# Quadrature_Mixers_FIXED.net
KiCad netlist of a schematic drawn in Altium Designer
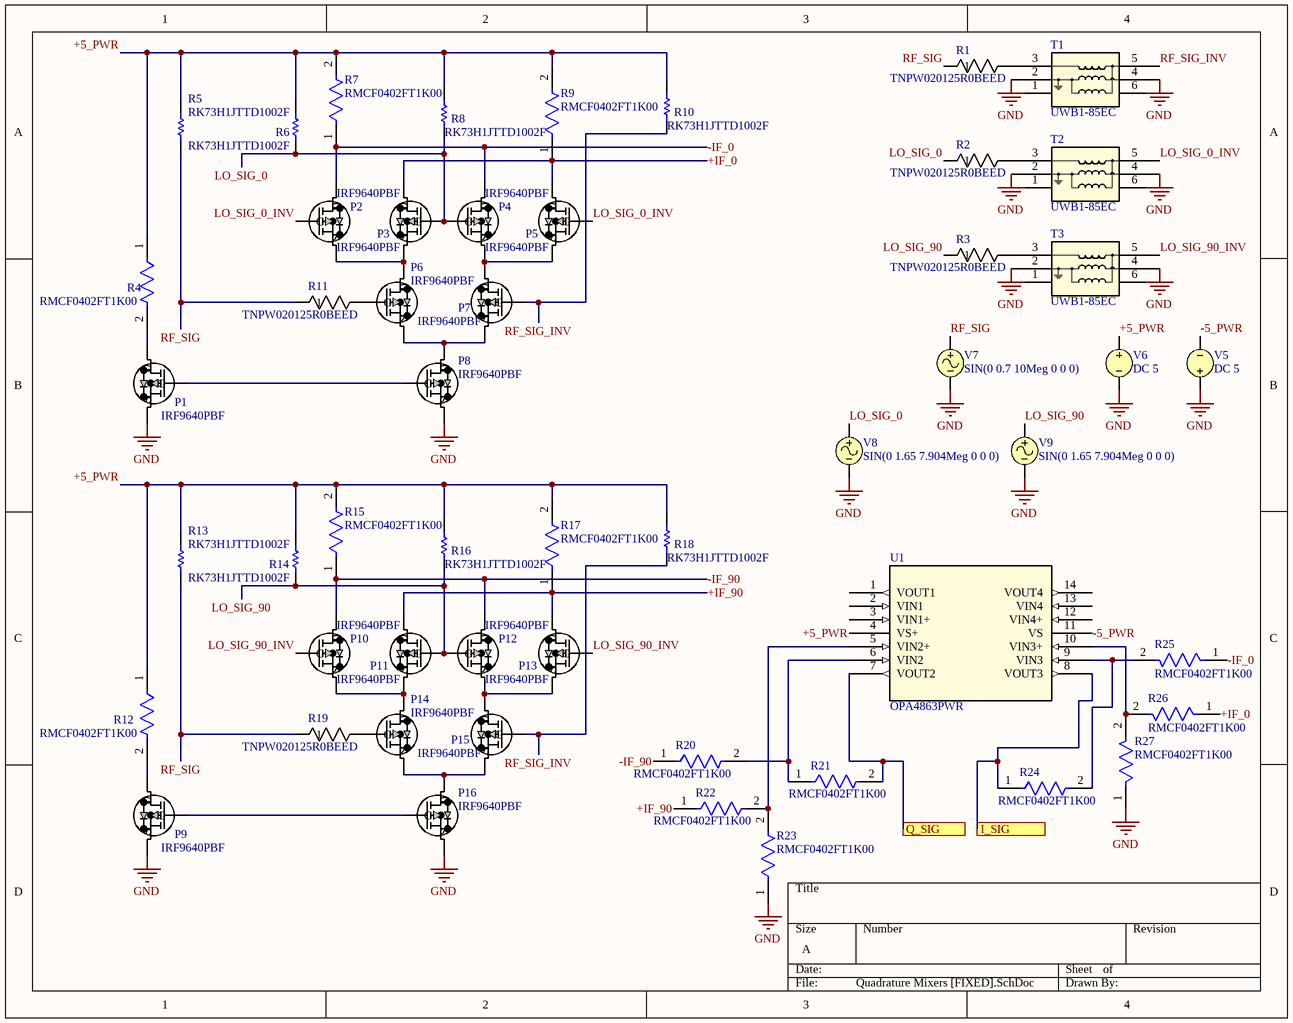
[diagram p0: Quadrature Mixers [FIXED].SchDoc]

(export (version "E")
  (design (tool "Eeschema 10.0.6"))
  (components
    (comp (ref "P1")
      (value "IRF9640PBF")
      (footprint "TO220AB_VIS")
      (description "No Description Available")
      (libsource (lib "IRF9640PBF") (part "IRF9640PBF"))
    )
    (comp (ref "P2")
      (value "IRF9640PBF")
      (footprint "TO220AB_VIS")
      (description "No Description Available")
      (libsource (lib "IRF9640PBF") (part "IRF9640PBF"))
    )
    (comp (ref "P3")
      (value "IRF9640PBF")
      (footprint "TO220AB_VIS")
      (description "No Description Available")
      (libsource (lib "IRF9640PBF") (part "IRF9640PBF"))
    )
    (comp (ref "P4")
      (value "IRF9640PBF")
      (footprint "TO220AB_VIS")
      (description "No Description Available")
      (libsource (lib "IRF9640PBF") (part "IRF9640PBF"))
    )
    (comp (ref "P5")
      (value "IRF9640PBF")
      (footprint "TO220AB_VIS")
      (description "No Description Available")
      (libsource (lib "IRF9640PBF") (part "IRF9640PBF"))
    )
    (comp (ref "P6")
      (value "IRF9640PBF")
      (footprint "TO220AB_VIS")
      (description "No Description Available")
      (libsource (lib "IRF9640PBF") (part "IRF9640PBF"))
    )
    (comp (ref "P7")
      (value "IRF9640PBF")
      (footprint "TO220AB_VIS")
      (description "No Description Available")
      (libsource (lib "IRF9640PBF") (part "IRF9640PBF"))
    )
    (comp (ref "P8")
      (value "IRF9640PBF")
      (footprint "TO220AB_VIS")
      (description "No Description Available")
      (libsource (lib "IRF9640PBF") (part "IRF9640PBF"))
    )
    (comp (ref "P9")
      (value "IRF9640PBF")
      (footprint "TO220AB_VIS")
      (description "No Description Available")
      (libsource (lib "IRF9640PBF") (part "IRF9640PBF"))
    )
    (comp (ref "P10")
      (value "IRF9640PBF")
      (footprint "TO220AB_VIS")
      (description "No Description Available")
      (libsource (lib "IRF9640PBF") (part "IRF9640PBF"))
    )
    (comp (ref "P11")
      (value "IRF9640PBF")
      (footprint "TO220AB_VIS")
      (description "No Description Available")
      (libsource (lib "IRF9640PBF") (part "IRF9640PBF"))
    )
    (comp (ref "P12")
      (value "IRF9640PBF")
      (footprint "TO220AB_VIS")
      (description "No Description Available")
      (libsource (lib "IRF9640PBF") (part "IRF9640PBF"))
    )
    (comp (ref "P13")
      (value "IRF9640PBF")
      (footprint "TO220AB_VIS")
      (description "No Description Available")
      (libsource (lib "IRF9640PBF") (part "IRF9640PBF"))
    )
    (comp (ref "P14")
      (value "IRF9640PBF")
      (footprint "TO220AB_VIS")
      (description "No Description Available")
      (libsource (lib "IRF9640PBF") (part "IRF9640PBF"))
    )
    (comp (ref "P15")
      (value "IRF9640PBF")
      (footprint "TO220AB_VIS")
      (description "No Description Available")
      (libsource (lib "IRF9640PBF") (part "IRF9640PBF"))
    )
    (comp (ref "P16")
      (value "IRF9640PBF")
      (footprint "TO220AB_VIS")
      (description "No Description Available")
      (libsource (lib "IRF9640PBF") (part "IRF9640PBF"))
    )
    (comp (ref "R1")
      (value "TNPW020125R0BEED")
      (footprint "RES_TNPW0201_VIS")
      (description "RES 25 OHM 0.1% 0.075W 0201")
      (libsource (lib "TNPW020125R0BEED") (part "TNPW020125R0BEED"))
    )
    (comp (ref "R2")
      (value "TNPW020125R0BEED")
      (footprint "RES_TNPW0201_VIS")
      (description "RES 25 OHM 0.1% 0.075W 0201")
      (libsource (lib "TNPW020125R0BEED") (part "TNPW020125R0BEED"))
    )
    (comp (ref "R3")
      (value "TNPW020125R0BEED")
      (footprint "RES_TNPW0201_VIS")
      (description "RES 25 OHM 0.1% 0.075W 0201")
      (libsource (lib "TNPW020125R0BEED") (part "TNPW020125R0BEED"))
    )
    (comp (ref "R4")
      (value "RMCF0402FT1K00")
      (footprint "FP-RMCF0402-MFG")
      (description "1kΩ ±1% 0.063W 0402 Thick Film Chip Resistor AEC-Q200 compliant")
      (fields (field (name "TOLERANCE") "1%"))
      (libsource (lib "Altium Content Vault") (part "1029c3af85768c4190bb7ad29bc67b5"))
    )
    (comp (ref "R5")
      (value "RK73H1JTTD1002F")
      (footprint "RESC1608X55X30ML20T10")
      (fields (field (name "MANUFACTURER") "KOA Speer"))
      (libsource (lib "Altium Content Vault") (part "RES"))
    )
    (comp (ref "R6")
      (value "RK73H1JTTD1002F")
      (footprint "RESC1608X55X30ML20T10")
      (fields (field (name "MANUFACTURER") "KOA Speer"))
      (libsource (lib "Altium Content Vault") (part "RES"))
    )
    (comp (ref "R7")
      (value "RMCF0402FT1K00")
      (footprint "FP-RMCF0402-MFG")
      (description "1kΩ ±1% 0.063W 0402 Thick Film Chip Resistor AEC-Q200 compliant")
      (fields (field (name "TOLERANCE") "1%"))
      (libsource (lib "Altium Content Vault") (part "1029c3af85768c4190bb7ad29bc67b5"))
    )
    (comp (ref "R8")
      (value "RK73H1JTTD1002F")
      (footprint "RESC1608X55X30ML20T10")
      (fields (field (name "MANUFACTURER") "KOA Speer"))
      (libsource (lib "Altium Content Vault") (part "RES"))
    )
    (comp (ref "R9")
      (value "RMCF0402FT1K00")
      (footprint "FP-RMCF0402-MFG")
      (description "1kΩ ±1% 0.063W 0402 Thick Film Chip Resistor AEC-Q200 compliant")
      (fields (field (name "TOLERANCE") "1%"))
      (libsource (lib "Altium Content Vault") (part "1029c3af85768c4190bb7ad29bc67b5"))
    )
    (comp (ref "R10")
      (value "RK73H1JTTD1002F")
      (footprint "RESC1608X55X30ML20T10")
      (fields (field (name "MANUFACTURER") "KOA Speer"))
      (libsource (lib "Altium Content Vault") (part "RES"))
    )
    (comp (ref "R11")
      (value "TNPW020125R0BEED")
      (footprint "RES_TNPW0201_VIS")
      (description "RES 25 OHM 0.1% 0.075W 0201")
      (libsource (lib "TNPW020125R0BEED") (part "TNPW020125R0BEED"))
    )
    (comp (ref "R12")
      (value "RMCF0402FT1K00")
      (footprint "FP-RMCF0402-MFG")
      (description "1kΩ ±1% 0.063W 0402 Thick Film Chip Resistor AEC-Q200 compliant")
      (fields (field (name "TOLERANCE") "1%"))
      (libsource (lib "Altium Content Vault") (part "1029c3af85768c4190bb7ad29bc67b5"))
    )
    (comp (ref "R13")
      (value "RK73H1JTTD1002F")
      (footprint "RESC1608X55X30ML20T10")
      (fields (field (name "MANUFACTURER") "KOA Speer"))
      (libsource (lib "Altium Content Vault") (part "RES"))
    )
    (comp (ref "R14")
      (value "RK73H1JTTD1002F")
      (footprint "RESC1608X55X30ML20T10")
      (fields (field (name "MANUFACTURER") "KOA Speer"))
      (libsource (lib "Altium Content Vault") (part "RES"))
    )
    (comp (ref "R15")
      (value "RMCF0402FT1K00")
      (footprint "FP-RMCF0402-MFG")
      (description "1kΩ ±1% 0.063W 0402 Thick Film Chip Resistor AEC-Q200 compliant")
      (fields (field (name "TOLERANCE") "1%"))
      (libsource (lib "Altium Content Vault") (part "1029c3af85768c4190bb7ad29bc67b5"))
    )
    (comp (ref "R16")
      (value "RK73H1JTTD1002F")
      (footprint "RESC1608X55X30ML20T10")
      (fields (field (name "MANUFACTURER") "KOA Speer"))
      (libsource (lib "Altium Content Vault") (part "RES"))
    )
    (comp (ref "R17")
      (value "RMCF0402FT1K00")
      (footprint "FP-RMCF0402-MFG")
      (description "1kΩ ±1% 0.063W 0402 Thick Film Chip Resistor AEC-Q200 compliant")
      (fields (field (name "TOLERANCE") "1%"))
      (libsource (lib "Altium Content Vault") (part "1029c3af85768c4190bb7ad29bc67b5"))
    )
    (comp (ref "R18")
      (value "RK73H1JTTD1002F")
      (footprint "RESC1608X55X30ML20T10")
      (fields (field (name "MANUFACTURER") "KOA Speer"))
      (libsource (lib "Altium Content Vault") (part "RES"))
    )
    (comp (ref "R19")
      (value "TNPW020125R0BEED")
      (footprint "RES_TNPW0201_VIS")
      (description "RES 25 OHM 0.1% 0.075W 0201")
      (libsource (lib "TNPW020125R0BEED") (part "TNPW020125R0BEED"))
    )
    (comp (ref "R20")
      (value "RMCF0402FT1K00")
      (footprint "FP-RMCF0402-MFG")
      (description "1kΩ ±1% 0.063W 0402 Thick Film Chip Resistor AEC-Q200 compliant")
      (fields (field (name "TOLERANCE") "1%"))
      (libsource (lib "Altium Content Vault") (part "1029c3af85768c4190bb7ad29bc67b5"))
    )
    (comp (ref "R21")
      (value "RMCF0402FT1K00")
      (footprint "FP-RMCF0402-MFG")
      (description "1kΩ ±1% 0.063W 0402 Thick Film Chip Resistor AEC-Q200 compliant")
      (fields (field (name "TOLERANCE") "1%"))
      (libsource (lib "Altium Content Vault") (part "1029c3af85768c4190bb7ad29bc67b5"))
    )
    (comp (ref "R22")
      (value "RMCF0402FT1K00")
      (footprint "FP-RMCF0402-MFG")
      (description "1kΩ ±1% 0.063W 0402 Thick Film Chip Resistor AEC-Q200 compliant")
      (fields (field (name "TOLERANCE") "1%"))
      (libsource (lib "Altium Content Vault") (part "1029c3af85768c4190bb7ad29bc67b5"))
    )
    (comp (ref "R23")
      (value "RMCF0402FT1K00")
      (footprint "FP-RMCF0402-MFG")
      (description "1kΩ ±1% 0.063W 0402 Thick Film Chip Resistor AEC-Q200 compliant")
      (fields (field (name "TOLERANCE") "1%"))
      (libsource (lib "Altium Content Vault") (part "1029c3af85768c4190bb7ad29bc67b5"))
    )
    (comp (ref "R24")
      (value "RMCF0402FT1K00")
      (footprint "FP-RMCF0402-MFG")
      (description "1kΩ ±1% 0.063W 0402 Thick Film Chip Resistor AEC-Q200 compliant")
      (fields (field (name "TOLERANCE") "1%"))
      (libsource (lib "Altium Content Vault") (part "1029c3af85768c4190bb7ad29bc67b5"))
    )
    (comp (ref "R25")
      (value "RMCF0402FT1K00")
      (footprint "FP-RMCF0402-MFG")
      (description "1kΩ ±1% 0.063W 0402 Thick Film Chip Resistor AEC-Q200 compliant")
      (fields (field (name "TOLERANCE") "1%"))
      (libsource (lib "Altium Content Vault") (part "1029c3af85768c4190bb7ad29bc67b5"))
    )
    (comp (ref "R26")
      (value "RMCF0402FT1K00")
      (footprint "FP-RMCF0402-MFG")
      (description "1kΩ ±1% 0.063W 0402 Thick Film Chip Resistor AEC-Q200 compliant")
      (fields (field (name "TOLERANCE") "1%"))
      (libsource (lib "Altium Content Vault") (part "1029c3af85768c4190bb7ad29bc67b5"))
    )
    (comp (ref "R27")
      (value "RMCF0402FT1K00")
      (footprint "FP-RMCF0402-MFG")
      (description "1kΩ ±1% 0.063W 0402 Thick Film Chip Resistor AEC-Q200 compliant")
      (fields (field (name "TOLERANCE") "1%"))
      (libsource (lib "Altium Content Vault") (part "1029c3af85768c4190bb7ad29bc67b5"))
    )
    (comp (ref "T1")
      (value "UWB1-85EC")
      (footprint "UWB1UWB2_COC")
      (libsource (lib "UWB1-85EC") (part "UWB1-85EC"))
    )
    (comp (ref "T2")
      (value "UWB1-85EC")
      (footprint "UWB1UWB2_COC")
      (libsource (lib "UWB1-85EC") (part "UWB1-85EC"))
    )
    (comp (ref "T3")
      (value "UWB1-85EC")
      (footprint "UWB1UWB2_COC")
      (libsource (lib "UWB1-85EC") (part "UWB1-85EC"))
    )
    (comp (ref "U1")
      (value "OPA4863PWR")
      (footprint "PW14_TEX")
      (description "No Description Available")
      (libsource (lib "OPA4863PWR") (part "OPA4863PWR"))
    )
    (comp (ref "V5")
      (value "DC 5")
      (description "Voltage Source")
      (fields (field (name "PUBLISHER") "Altium Limited"))
      (libsource (lib "Simulation Generic Components") (part "VSRC"))
    )
    (comp (ref "V6")
      (value "DC 5")
      (description "Voltage Source")
      (fields (field (name "PUBLISHER") "Altium Limited"))
      (libsource (lib "Simulation Generic Components") (part "VSRC"))
    )
    (comp (ref "V7")
      (value "SIN(0 0.7 10Meg 0 0 0)")
      (description "Sinusoidal Voltage Source")
      (fields (field (name "PUBLISHER") "Altium Limited"))
      (libsource (lib "Simulation Generic Components") (part "VSIN"))
    )
    (comp (ref "V8")
      (value "SIN(0 1.65 7.904Meg 0 0 0)")
      (description "Sinusoidal Voltage Source")
      (fields (field (name "PUBLISHER") "Altium Limited"))
      (libsource (lib "Simulation Generic Components") (part "VSIN"))
    )
    (comp (ref "V9")
      (value "SIN(0 1.65 7.904Meg 0 0 0)")
      (description "Sinusoidal Voltage Source")
      (fields (field (name "PUBLISHER") "Altium Limited"))
      (libsource (lib "Simulation Generic Components") (part "VSIN"))
    )
  )
  (nets
    (net (code "1") (name "/+5_PWR") (class "Default")
      (node (ref "R10") (pin "2") (pinfunction "2_2") (pintype "passive"))
      (node (ref "R12") (pin "1") (pinfunction "1_1") (pintype "passive"))
      (node (ref "R13") (pin "2") (pinfunction "2_2") (pintype "passive"))
      (node (ref "R14") (pin "2") (pinfunction "2_2") (pintype "passive"))
      (node (ref "R15") (pin "2") (pinfunction "2_2") (pintype "passive"))
      (node (ref "R16") (pin "2") (pinfunction "2_2") (pintype "passive"))
      (node (ref "R17") (pin "2") (pinfunction "2_2") (pintype "passive"))
      (node (ref "R18") (pin "2") (pinfunction "2_2") (pintype "passive"))
      (node (ref "R4") (pin "1") (pinfunction "1_1") (pintype "passive"))
      (node (ref "R5") (pin "2") (pinfunction "2_2") (pintype "passive"))
      (node (ref "R6") (pin "2") (pinfunction "2_2") (pintype "passive"))
      (node (ref "R7") (pin "2") (pinfunction "2_2") (pintype "passive"))
      (node (ref "R8") (pin "2") (pinfunction "2_2") (pintype "passive"))
      (node (ref "R9") (pin "2") (pinfunction "2_2") (pintype "passive"))
      (node (ref "U1") (pin "4") (pinfunction "VS+_4") (pintype "power_in"))
      (node (ref "V6") (pin "1") (pinfunction "1_1") (pintype "passive"))
    )
    (net (code "2") (name "/+IF_0") (class "Default")
      (node (ref "P3") (pin "2") (pinfunction "D_2") (pintype "passive"))
      (node (ref "P5") (pin "2") (pinfunction "D_2") (pintype "passive"))
      (node (ref "R26") (pin "1") (pinfunction "1_1") (pintype "passive"))
      (node (ref "R9") (pin "1") (pinfunction "1_1") (pintype "passive"))
    )
    (net (code "3") (name "/+IF_90") (class "Default")
      (node (ref "P11") (pin "2") (pinfunction "D_2") (pintype "passive"))
      (node (ref "P13") (pin "2") (pinfunction "D_2") (pintype "passive"))
      (node (ref "R17") (pin "1") (pinfunction "1_1") (pintype "passive"))
      (node (ref "R22") (pin "1") (pinfunction "1_1") (pintype "passive"))
    )
    (net (code "4") (name "/-5_PWR") (class "Default")
      (node (ref "U1") (pin "11") (pinfunction "VS_11") (pintype "power_in"))
      (node (ref "V5") (pin "2") (pinfunction "2_2") (pintype "passive"))
    )
    (net (code "5") (name "/-IF_0") (class "Default")
      (node (ref "P2") (pin "2") (pinfunction "D_2") (pintype "passive"))
      (node (ref "P4") (pin "2") (pinfunction "D_2") (pintype "passive"))
      (node (ref "R25") (pin "1") (pinfunction "1_1") (pintype "passive"))
      (node (ref "R7") (pin "1") (pinfunction "1_1") (pintype "passive"))
    )
    (net (code "6") (name "/-IF_90") (class "Default")
      (node (ref "P10") (pin "2") (pinfunction "D_2") (pintype "passive"))
      (node (ref "P12") (pin "2") (pinfunction "D_2") (pintype "passive"))
      (node (ref "R15") (pin "1") (pinfunction "1_1") (pintype "passive"))
      (node (ref "R20") (pin "1") (pinfunction "1_1") (pintype "passive"))
    )
    (net (code "7") (name "/I_SIG") (class "Default")
      (node (ref "R24") (pin "1") (pinfunction "1_1") (pintype "passive"))
      (node (ref "U1") (pin "8") (pinfunction "VOUT3_8") (pintype "output"))
    )
    (net (code "8") (name "/LO_SIG_0") (class "Default")
      (node (ref "P3") (pin "1") (pinfunction "G_1") (pintype "passive"))
      (node (ref "P4") (pin "1") (pinfunction "G_1") (pintype "passive"))
      (node (ref "R2") (pin "1") (pinfunction "1_1") (pintype "passive"))
      (node (ref "R6") (pin "1") (pinfunction "1_1") (pintype "passive"))
      (node (ref "R8") (pin "1") (pinfunction "1_1") (pintype "passive"))
      (node (ref "V8") (pin "1") (pinfunction "1_1") (pintype "passive"))
    )
    (net (code "9") (name "/LO_SIG_0_INV") (class "Default")
      (node (ref "P2") (pin "1") (pinfunction "G_1") (pintype "passive"))
      (node (ref "P5") (pin "1") (pinfunction "G_1") (pintype "passive"))
      (node (ref "T2") (pin "5") (pinfunction "5_5") (pintype "passive"))
    )
    (net (code "10") (name "/LO_SIG_90") (class "Default")
      (node (ref "P11") (pin "1") (pinfunction "G_1") (pintype "passive"))
      (node (ref "P12") (pin "1") (pinfunction "G_1") (pintype "passive"))
      (node (ref "R14") (pin "1") (pinfunction "1_1") (pintype "passive"))
      (node (ref "R16") (pin "1") (pinfunction "1_1") (pintype "passive"))
      (node (ref "R3") (pin "1") (pinfunction "1_1") (pintype "passive"))
      (node (ref "V9") (pin "1") (pinfunction "1_1") (pintype "passive"))
    )
    (net (code "11") (name "/LO_SIG_90_INV") (class "Default")
      (node (ref "P10") (pin "1") (pinfunction "G_1") (pintype "passive"))
      (node (ref "P13") (pin "1") (pinfunction "G_1") (pintype "passive"))
      (node (ref "T3") (pin "5") (pinfunction "5_5") (pintype "passive"))
    )
    (net (code "12") (name "/Q_SIG") (class "Default")
      (node (ref "R21") (pin "2") (pinfunction "2_2") (pintype "passive"))
      (node (ref "U1") (pin "7") (pinfunction "VOUT2_7") (pintype "output"))
    )
    (net (code "13") (name "/RF_SIG") (class "Default")
      (node (ref "R1") (pin "1") (pinfunction "1_1") (pintype "passive"))
      (node (ref "R11") (pin "1") (pinfunction "1_1") (pintype "passive"))
      (node (ref "R13") (pin "1") (pinfunction "1_1") (pintype "passive"))
      (node (ref "R19") (pin "1") (pinfunction "1_1") (pintype "passive"))
      (node (ref "R5") (pin "1") (pinfunction "1_1") (pintype "passive"))
      (node (ref "V7") (pin "1") (pinfunction "1_1") (pintype "passive"))
    )
    (net (code "14") (name "/RF_SIG_INV") (class "Default")
      (node (ref "P15") (pin "1") (pinfunction "G_1") (pintype "passive"))
      (node (ref "P7") (pin "1") (pinfunction "G_1") (pintype "passive"))
      (node (ref "R10") (pin "1") (pinfunction "1_1") (pintype "passive"))
      (node (ref "R18") (pin "1") (pinfunction "1_1") (pintype "passive"))
      (node (ref "T1") (pin "5") (pinfunction "5_5") (pintype "passive"))
    )
    (net (code "15") (name "GND") (class "Default")
      (node (ref "P1") (pin "3") (pinfunction "S_3") (pintype "passive"))
      (node (ref "P16") (pin "3") (pinfunction "S_3") (pintype "passive"))
      (node (ref "P8") (pin "3") (pinfunction "S_3") (pintype "passive"))
      (node (ref "P9") (pin "3") (pinfunction "S_3") (pintype "passive"))
      (node (ref "R23") (pin "1") (pinfunction "1_1") (pintype "passive"))
      (node (ref "R27") (pin "1") (pinfunction "1_1") (pintype "passive"))
      (node (ref "T1") (pin "2") (pinfunction "2_2") (pintype "passive"))
      (node (ref "T1") (pin "4") (pinfunction "4_4") (pintype "passive"))
      (node (ref "T2") (pin "2") (pinfunction "2_2") (pintype "passive"))
      (node (ref "T2") (pin "4") (pinfunction "4_4") (pintype "passive"))
      (node (ref "T3") (pin "2") (pinfunction "2_2") (pintype "passive"))
      (node (ref "T3") (pin "4") (pinfunction "4_4") (pintype "passive"))
      (node (ref "V5") (pin "1") (pinfunction "1_1") (pintype "passive"))
      (node (ref "V6") (pin "2") (pinfunction "2_2") (pintype "passive"))
      (node (ref "V7") (pin "2") (pinfunction "2_2") (pintype "passive"))
      (node (ref "V8") (pin "2") (pinfunction "2_2") (pintype "passive"))
      (node (ref "V9") (pin "2") (pinfunction "2_2") (pintype "passive"))
    )
    (net (code "16") (name "Net-(P1-D)") (class "Default")
      (node (ref "P1") (pin "2") (pinfunction "D_2") (pintype "passive"))
      (node (ref "R4") (pin "2") (pinfunction "2_2") (pintype "passive"))
    )
    (net (code "17") (name "Net-(P1-G)") (class "Default")
      (node (ref "P1") (pin "1") (pinfunction "G_1") (pintype "passive"))
      (node (ref "P8") (pin "1") (pinfunction "G_1") (pintype "passive"))
    )
    (net (code "18") (name "Net-(P2-S)") (class "Default")
      (node (ref "P2") (pin "3") (pinfunction "S_3") (pintype "passive"))
      (node (ref "P3") (pin "3") (pinfunction "S_3") (pintype "passive"))
      (node (ref "P6") (pin "2") (pinfunction "D_2") (pintype "passive"))
    )
    (net (code "19") (name "Net-(P4-S)") (class "Default")
      (node (ref "P4") (pin "3") (pinfunction "S_3") (pintype "passive"))
      (node (ref "P5") (pin "3") (pinfunction "S_3") (pintype "passive"))
      (node (ref "P7") (pin "2") (pinfunction "D_2") (pintype "passive"))
    )
    (net (code "20") (name "Net-(P6-G)") (class "Default")
      (node (ref "P6") (pin "1") (pinfunction "G_1") (pintype "passive"))
      (node (ref "R11") (pin "2") (pinfunction "2_2") (pintype "passive"))
    )
    (net (code "21") (name "Net-(P6-S)") (class "Default")
      (node (ref "P6") (pin "3") (pinfunction "S_3") (pintype "passive"))
      (node (ref "P7") (pin "3") (pinfunction "S_3") (pintype "passive"))
      (node (ref "P8") (pin "2") (pinfunction "D_2") (pintype "passive"))
    )
    (net (code "22") (name "Net-(P9-D)") (class "Default")
      (node (ref "P9") (pin "2") (pinfunction "D_2") (pintype "passive"))
      (node (ref "R12") (pin "2") (pinfunction "2_2") (pintype "passive"))
    )
    (net (code "23") (name "Net-(P10-S)") (class "Default")
      (node (ref "P10") (pin "3") (pinfunction "S_3") (pintype "passive"))
      (node (ref "P11") (pin "3") (pinfunction "S_3") (pintype "passive"))
      (node (ref "P14") (pin "2") (pinfunction "D_2") (pintype "passive"))
    )
    (net (code "24") (name "Net-(P12-S)") (class "Default")
      (node (ref "P12") (pin "3") (pinfunction "S_3") (pintype "passive"))
      (node (ref "P13") (pin "3") (pinfunction "S_3") (pintype "passive"))
      (node (ref "P15") (pin "2") (pinfunction "D_2") (pintype "passive"))
    )
    (net (code "25") (name "Net-(P14-G)") (class "Default")
      (node (ref "P14") (pin "1") (pinfunction "G_1") (pintype "passive"))
      (node (ref "R19") (pin "2") (pinfunction "2_2") (pintype "passive"))
    )
    (net (code "26") (name "Net-(P14-S)") (class "Default")
      (node (ref "P14") (pin "3") (pinfunction "S_3") (pintype "passive"))
      (node (ref "P15") (pin "3") (pinfunction "S_3") (pintype "passive"))
      (node (ref "P16") (pin "2") (pinfunction "D_2") (pintype "passive"))
    )
    (net (code "27") (name "Net-(P16-G)") (class "Default")
      (node (ref "P16") (pin "1") (pinfunction "G_1") (pintype "passive"))
      (node (ref "P9") (pin "1") (pinfunction "G_1") (pintype "passive"))
    )
    (net (code "28") (name "Net-(R1-Pad2)") (class "Default")
      (node (ref "R1") (pin "2") (pinfunction "2_2") (pintype "passive"))
      (node (ref "T1") (pin "3") (pinfunction "3_3") (pintype "passive"))
    )
    (net (code "29") (name "Net-(R2-Pad2)") (class "Default")
      (node (ref "R2") (pin "2") (pinfunction "2_2") (pintype "passive"))
      (node (ref "T2") (pin "3") (pinfunction "3_3") (pintype "passive"))
    )
    (net (code "30") (name "Net-(R3-Pad2)") (class "Default")
      (node (ref "R3") (pin "2") (pinfunction "2_2") (pintype "passive"))
      (node (ref "T3") (pin "3") (pinfunction "3_3") (pintype "passive"))
    )
    (net (code "31") (name "Net-(U1-VIN2)") (class "Default")
      (node (ref "R20") (pin "2") (pinfunction "2_2") (pintype "passive"))
      (node (ref "R21") (pin "1") (pinfunction "1_1") (pintype "passive"))
      (node (ref "U1") (pin "6") (pinfunction "VIN2_6") (pintype "input"))
    )
    (net (code "32") (name "Net-(U1-VIN2+)") (class "Default")
      (node (ref "R22") (pin "2") (pinfunction "2_2") (pintype "passive"))
      (node (ref "R23") (pin "2") (pinfunction "2_2") (pintype "passive"))
      (node (ref "U1") (pin "5") (pinfunction "VIN2+_5") (pintype "input"))
    )
    (net (code "33") (name "Net-(U1-VIN3)") (class "Default")
      (node (ref "R24") (pin "2") (pinfunction "2_2") (pintype "passive"))
      (node (ref "R25") (pin "2") (pinfunction "2_2") (pintype "passive"))
      (node (ref "U1") (pin "9") (pinfunction "VIN3_9") (pintype "input"))
    )
    (net (code "34") (name "Net-(U1-VIN3+)") (class "Default")
      (node (ref "R26") (pin "2") (pinfunction "2_2") (pintype "passive"))
      (node (ref "R27") (pin "2") (pinfunction "2_2") (pintype "passive"))
      (node (ref "U1") (pin "10") (pinfunction "VIN3+_10") (pintype "input"))
    )
    (net (code "35") (name "unconnected-(T1-Pad1)") (class "Default")
      (node (ref "T1") (pin "1") (pinfunction "1_1") (pintype "passive"))
    )
    (net (code "36") (name "unconnected-(T1-Pad6)") (class "Default")
      (node (ref "T1") (pin "6") (pinfunction "6_6") (pintype "passive"))
    )
    (net (code "37") (name "unconnected-(T2-Pad1)") (class "Default")
      (node (ref "T2") (pin "1") (pinfunction "1_1") (pintype "passive"))
    )
    (net (code "38") (name "unconnected-(T2-Pad6)") (class "Default")
      (node (ref "T2") (pin "6") (pinfunction "6_6") (pintype "passive"))
    )
    (net (code "39") (name "unconnected-(T3-Pad1)") (class "Default")
      (node (ref "T3") (pin "1") (pinfunction "1_1") (pintype "passive"))
    )
    (net (code "40") (name "unconnected-(T3-Pad6)") (class "Default")
      (node (ref "T3") (pin "6") (pinfunction "6_6") (pintype "passive"))
    )
    (net (code "41") (name "unconnected-(U1-VIN1+-Pad3)") (class "Default")
      (node (ref "U1") (pin "3") (pinfunction "VIN1+_3") (pintype "input"))
    )
    (net (code "42") (name "unconnected-(U1-VIN1-Pad2)") (class "Default")
      (node (ref "U1") (pin "2") (pinfunction "VIN1_2") (pintype "input"))
    )
    (net (code "43") (name "unconnected-(U1-VIN4+-Pad12)") (class "Default")
      (node (ref "U1") (pin "12") (pinfunction "VIN4+_12") (pintype "input"))
    )
    (net (code "44") (name "unconnected-(U1-VIN4-Pad13)") (class "Default")
      (node (ref "U1") (pin "13") (pinfunction "VIN4_13") (pintype "input"))
    )
    (net (code "45") (name "unconnected-(U1-VOUT1-Pad1)") (class "Default")
      (node (ref "U1") (pin "1") (pinfunction "VOUT1_1") (pintype "output"))
    )
    (net (code "46") (name "unconnected-(U1-VOUT4-Pad14)") (class "Default")
      (node (ref "U1") (pin "14") (pinfunction "VOUT4_14") (pintype "output"))
    )
  )
)
